# obc-v2_EXP-I2C-IRQ.net
KiCad netlist of a schematic drawn in Altium Designer
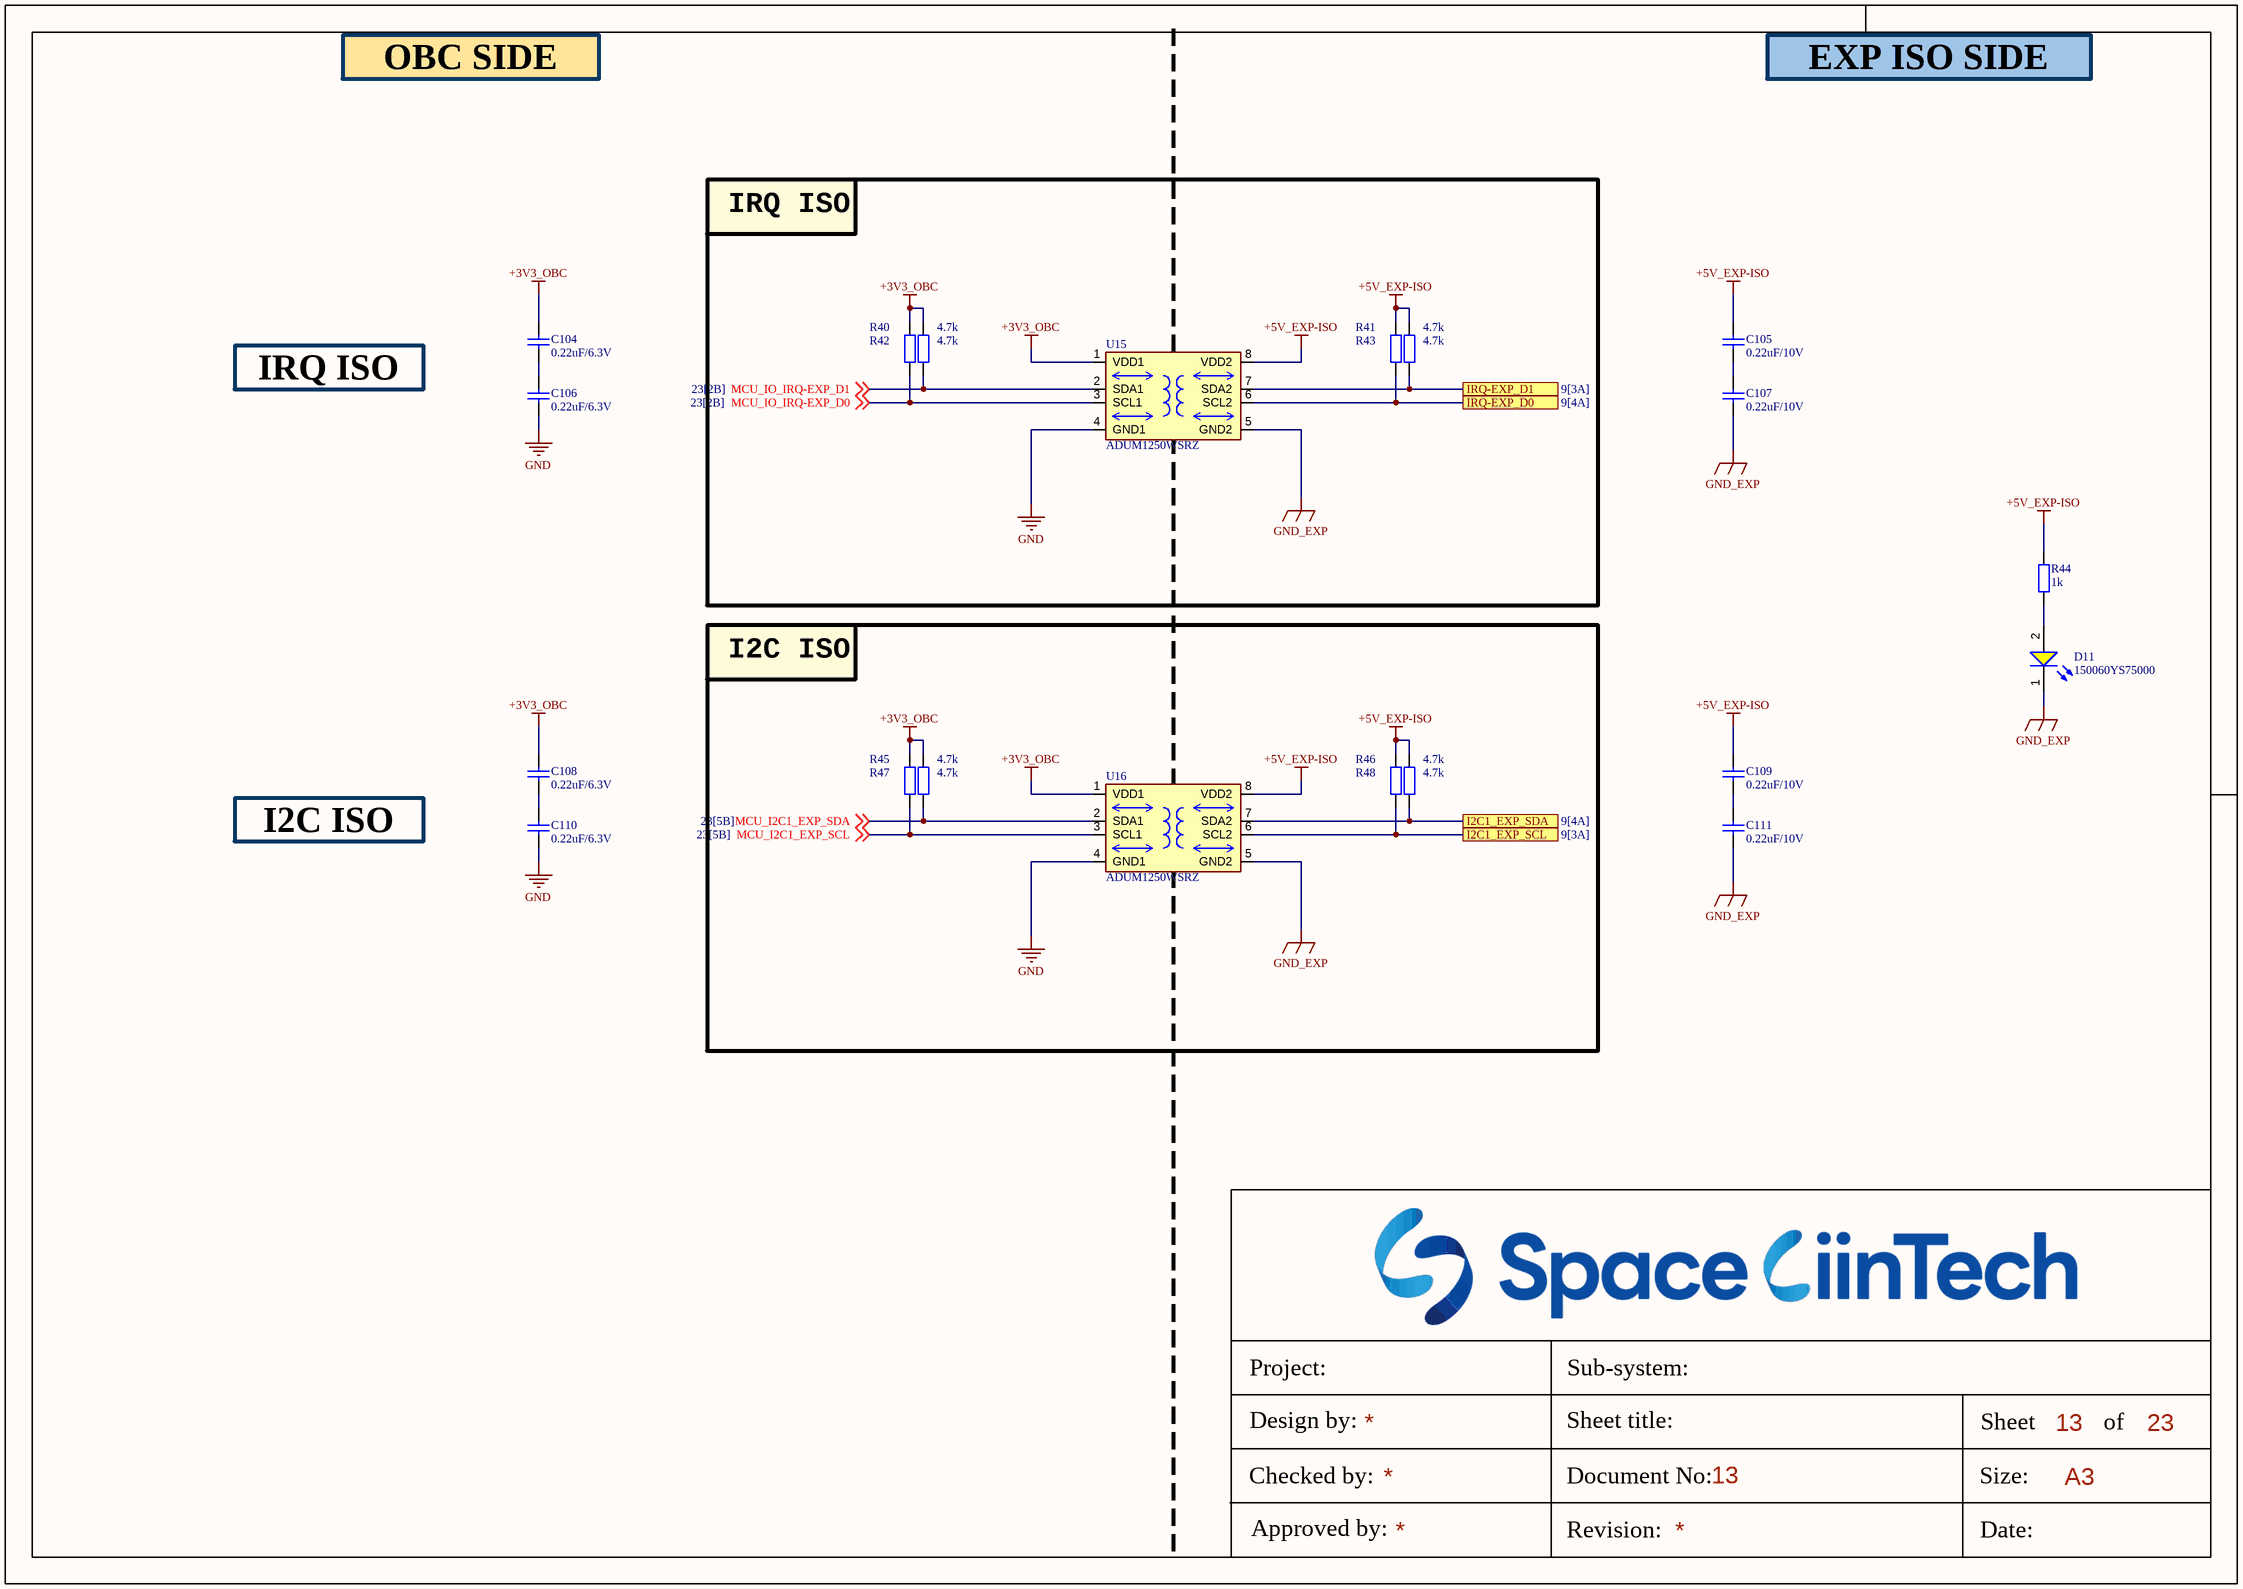
[diagram p0: obc-v2_EXP-I2C-IRQ.SchDoc]

(export (version "E")
  (design (tool "Eeschema 10.0.6"))
  (components
    (comp (ref "C104")
      (value "0.22uF/6.3V")
      (footprint "CAP_C_1005X60")
      (description "CAPC")
      (libsource (lib "Altium_Lib_by_KhueNguyenCreator") (part "Tu 0402 33nF 10V"))
    )
    (comp (ref "C105")
      (value "0.22uF/10V")
      (footprint "CAP_C_1005X60")
      (description "CAPC")
      (libsource (lib "Altium_Lib_by_KhueNguyenCreator") (part "Tu 0402 33nF 10V"))
    )
    (comp (ref "C106")
      (value "0.22uF/6.3V")
      (footprint "CAP_C_1005X60")
      (description "CAPC")
      (libsource (lib "Altium_Lib_by_KhueNguyenCreator") (part "Tu 0402 33nF 10V"))
    )
    (comp (ref "C107")
      (value "0.22uF/10V")
      (footprint "CAP_C_1005X60")
      (description "CAPC")
      (libsource (lib "Altium_Lib_by_KhueNguyenCreator") (part "Tu 0402 33nF 10V"))
    )
    (comp (ref "C108")
      (value "0.22uF/6.3V")
      (footprint "CAP_C_1005X60")
      (description "CAPC")
      (libsource (lib "Altium_Lib_by_KhueNguyenCreator") (part "Tu 0402 33nF 10V"))
    )
    (comp (ref "C109")
      (value "0.22uF/10V")
      (footprint "CAP_C_1005X60")
      (description "CAPC")
      (libsource (lib "Altium_Lib_by_KhueNguyenCreator") (part "Tu 0402 33nF 10V"))
    )
    (comp (ref "C110")
      (value "0.22uF/6.3V")
      (footprint "CAP_C_1005X60")
      (description "CAPC")
      (libsource (lib "Altium_Lib_by_KhueNguyenCreator") (part "Tu 0402 33nF 10V"))
    )
    (comp (ref "C111")
      (value "0.22uF/10V")
      (footprint "CAP_C_1005X60")
      (description "CAPC")
      (libsource (lib "Altium_Lib_by_KhueNguyenCreator") (part "Tu 0402 33nF 10V"))
    )
    (comp (ref "D11")
      (value "150060YS75000")
      (footprint "WL-SMCW_0603_150060xx75000")
      (description "LED YELLOW CLEAR 0603 SMD")
      (libsource (lib "Altium Content Vault") (part "LED_Yellow_2A-1K"))
    )
    (comp (ref "R40")
      (value "4.7k")
      (footprint "RES_C_1608X60")
      (description "RES")
      (libsource (lib "Altium_Lib_by_KhueNguyenCreator") (part "Tro 0603 1% 10k"))
    )
    (comp (ref "R41")
      (value "4.7k")
      (footprint "RES_C_1608X60")
      (description "RES")
      (libsource (lib "Altium_Lib_by_KhueNguyenCreator") (part "Tro 0603 1% 10k"))
    )
    (comp (ref "R42")
      (value "4.7k")
      (footprint "RES_C_1608X60")
      (description "RES")
      (libsource (lib "Altium_Lib_by_KhueNguyenCreator") (part "Tro 0603 1% 10k"))
    )
    (comp (ref "R43")
      (value "4.7k")
      (footprint "RES_C_1608X60")
      (description "RES")
      (libsource (lib "Altium_Lib_by_KhueNguyenCreator") (part "Tro 0603 1% 10k"))
    )
    (comp (ref "R44")
      (value "1k")
      (footprint "RES_C_1608X60")
      (description "RES")
      (libsource (lib "Altium_Lib_by_KhueNguyenCreator") (part "Tro 0603 1% 10k"))
    )
    (comp (ref "R45")
      (value "4.7k")
      (footprint "RES_C_1608X60")
      (description "RES")
      (libsource (lib "Altium_Lib_by_KhueNguyenCreator") (part "Tro 0603 1% 10k"))
    )
    (comp (ref "R46")
      (value "4.7k")
      (footprint "RES_C_1608X60")
      (description "RES")
      (libsource (lib "Altium_Lib_by_KhueNguyenCreator") (part "Tro 0603 1% 10k"))
    )
    (comp (ref "R47")
      (value "4.7k")
      (footprint "RES_C_1608X60")
      (description "RES")
      (libsource (lib "Altium_Lib_by_KhueNguyenCreator") (part "Tro 0603 1% 10k"))
    )
    (comp (ref "R48")
      (value "4.7k")
      (footprint "RES_C_1608X60")
      (description "RES")
      (libsource (lib "Altium_Lib_by_KhueNguyenCreator") (part "Tro 0603 1% 10k"))
    )
    (comp (ref "U15")
      (value "ADUM1250WSRZ")
      (footprint "SOIC127P602X173-8N")
      (description "I虏C Digital Isolator 2500Vrms 2 Channel 1Mbps 25kV/碌s CMTI 8-SOIC (0.154\", 3.90mm Width)")
      (fields (field (name "MF") "Analog Devices") (field (name "MP") "ADUM1250"))
      (libsource (lib "ADUM1250") (part "ADUM1250"))
    )
    (comp (ref "U16")
      (value "ADUM1250WSRZ")
      (footprint "SOIC127P602X173-8N")
      (description "I虏C Digital Isolator 2500Vrms 2 Channel 1Mbps 25kV/碌s CMTI 8-SOIC (0.154\", 3.90mm Width)")
      (fields (field (name "MF") "Analog Devices") (field (name "MP") "ADUM1250"))
      (libsource (lib "ADUM1250") (part "ADUM1250"))
    )
  )
  (nets
    (net (code "1") (name "+3V3_OBC") (class "Default")
      (node (ref "C104") (pin "1") (pinfunction "1_1") (pintype "passive"))
      (node (ref "C108") (pin "1") (pinfunction "1_1") (pintype "passive"))
      (node (ref "R40") (pin "2") (pinfunction "2_2") (pintype "passive"))
      (node (ref "R42") (pin "2") (pinfunction "2_2") (pintype "passive"))
      (node (ref "R45") (pin "2") (pinfunction "2_2") (pintype "passive"))
      (node (ref "R47") (pin "2") (pinfunction "2_2") (pintype "passive"))
      (node (ref "U15") (pin "1") (pinfunction "VDD1_1") (pintype "power_in"))
      (node (ref "U16") (pin "1") (pinfunction "VDD1_1") (pintype "power_in"))
    )
    (net (code "2") (name "+5V_EXP-ISO") (class "Default")
      (node (ref "C105") (pin "1") (pinfunction "1_1") (pintype "passive"))
      (node (ref "C109") (pin "1") (pinfunction "1_1") (pintype "passive"))
      (node (ref "R41") (pin "2") (pinfunction "2_2") (pintype "passive"))
      (node (ref "R43") (pin "2") (pinfunction "2_2") (pintype "passive"))
      (node (ref "R44") (pin "2") (pinfunction "2_2") (pintype "passive"))
      (node (ref "R46") (pin "2") (pinfunction "2_2") (pintype "passive"))
      (node (ref "R48") (pin "2") (pinfunction "2_2") (pintype "passive"))
      (node (ref "U15") (pin "8") (pinfunction "VDD2_8") (pintype "power_in"))
      (node (ref "U16") (pin "8") (pinfunction "VDD2_8") (pintype "power_in"))
    )
    (net (code "3") (name "/I2C1_EXP_SCL") (class "Default")
      (node (ref "R46") (pin "1") (pinfunction "1_1") (pintype "passive"))
      (node (ref "U16") (pin "6") (pinfunction "SCL2_6") (pintype "bidirectional"))
    )
    (net (code "4") (name "/I2C1_EXP_SDA") (class "Default")
      (node (ref "R48") (pin "1") (pinfunction "1_1") (pintype "passive"))
      (node (ref "U16") (pin "7") (pinfunction "SDA2_7") (pintype "bidirectional"))
    )
    (net (code "5") (name "/IRQ-EXP_D0") (class "Default")
      (node (ref "R41") (pin "1") (pinfunction "1_1") (pintype "passive"))
      (node (ref "U15") (pin "6") (pinfunction "SCL2_6") (pintype "bidirectional"))
    )
    (net (code "6") (name "/IRQ-EXP_D1") (class "Default")
      (node (ref "R43") (pin "1") (pinfunction "1_1") (pintype "passive"))
      (node (ref "U15") (pin "7") (pinfunction "SDA2_7") (pintype "bidirectional"))
    )
    (net (code "7") (name "GND") (class "Default")
      (node (ref "C106") (pin "2") (pinfunction "2_2") (pintype "passive"))
      (node (ref "C110") (pin "2") (pinfunction "2_2") (pintype "passive"))
      (node (ref "U15") (pin "4") (pinfunction "GND1_4") (pintype "power_in"))
      (node (ref "U16") (pin "4") (pinfunction "GND1_4") (pintype "power_in"))
    )
    (net (code "8") (name "GND_EXP") (class "Default")
      (node (ref "C107") (pin "2") (pinfunction "2_2") (pintype "passive"))
      (node (ref "C111") (pin "2") (pinfunction "2_2") (pintype "passive"))
      (node (ref "D11") (pin "1") (pinfunction "K_1") (pintype "passive"))
      (node (ref "U15") (pin "5") (pinfunction "GND2_5") (pintype "power_in"))
      (node (ref "U16") (pin "5") (pinfunction "GND2_5") (pintype "power_in"))
    )
    (net (code "9") (name "MCU_I2C1_EXP_SCL") (class "Default")
      (node (ref "R45") (pin "1") (pinfunction "1_1") (pintype "passive"))
      (node (ref "U16") (pin "3") (pinfunction "SCL1_3") (pintype "bidirectional"))
    )
    (net (code "10") (name "MCU_I2C1_EXP_SDA") (class "Default")
      (node (ref "R47") (pin "1") (pinfunction "1_1") (pintype "passive"))
      (node (ref "U16") (pin "2") (pinfunction "SDA1_2") (pintype "bidirectional"))
    )
    (net (code "11") (name "MCU_IO_IRQ-EXP_D0") (class "Default")
      (node (ref "R40") (pin "1") (pinfunction "1_1") (pintype "passive"))
      (node (ref "U15") (pin "3") (pinfunction "SCL1_3") (pintype "bidirectional"))
    )
    (net (code "12") (name "MCU_IO_IRQ-EXP_D1") (class "Default")
      (node (ref "R42") (pin "1") (pinfunction "1_1") (pintype "passive"))
      (node (ref "U15") (pin "2") (pinfunction "SDA1_2") (pintype "bidirectional"))
    )
    (net (code "13") (name "Net-(C104-Pad2)") (class "Default")
      (node (ref "C104") (pin "2") (pinfunction "2_2") (pintype "passive"))
      (node (ref "C106") (pin "1") (pinfunction "1_1") (pintype "passive"))
    )
    (net (code "14") (name "Net-(C105-Pad2)") (class "Default")
      (node (ref "C105") (pin "2") (pinfunction "2_2") (pintype "passive"))
      (node (ref "C107") (pin "1") (pinfunction "1_1") (pintype "passive"))
    )
    (net (code "15") (name "Net-(C108-Pad2)") (class "Default")
      (node (ref "C108") (pin "2") (pinfunction "2_2") (pintype "passive"))
      (node (ref "C110") (pin "1") (pinfunction "1_1") (pintype "passive"))
    )
    (net (code "16") (name "Net-(C109-Pad2)") (class "Default")
      (node (ref "C109") (pin "2") (pinfunction "2_2") (pintype "passive"))
      (node (ref "C111") (pin "1") (pinfunction "1_1") (pintype "passive"))
    )
    (net (code "17") (name "Net-(D11-A)") (class "Default")
      (node (ref "D11") (pin "2") (pinfunction "A_2") (pintype "passive"))
      (node (ref "R44") (pin "1") (pinfunction "1_1") (pintype "passive"))
    )
  )
)
